# MAIN.net
KiCad netlist of a schematic drawn in Altium Designer
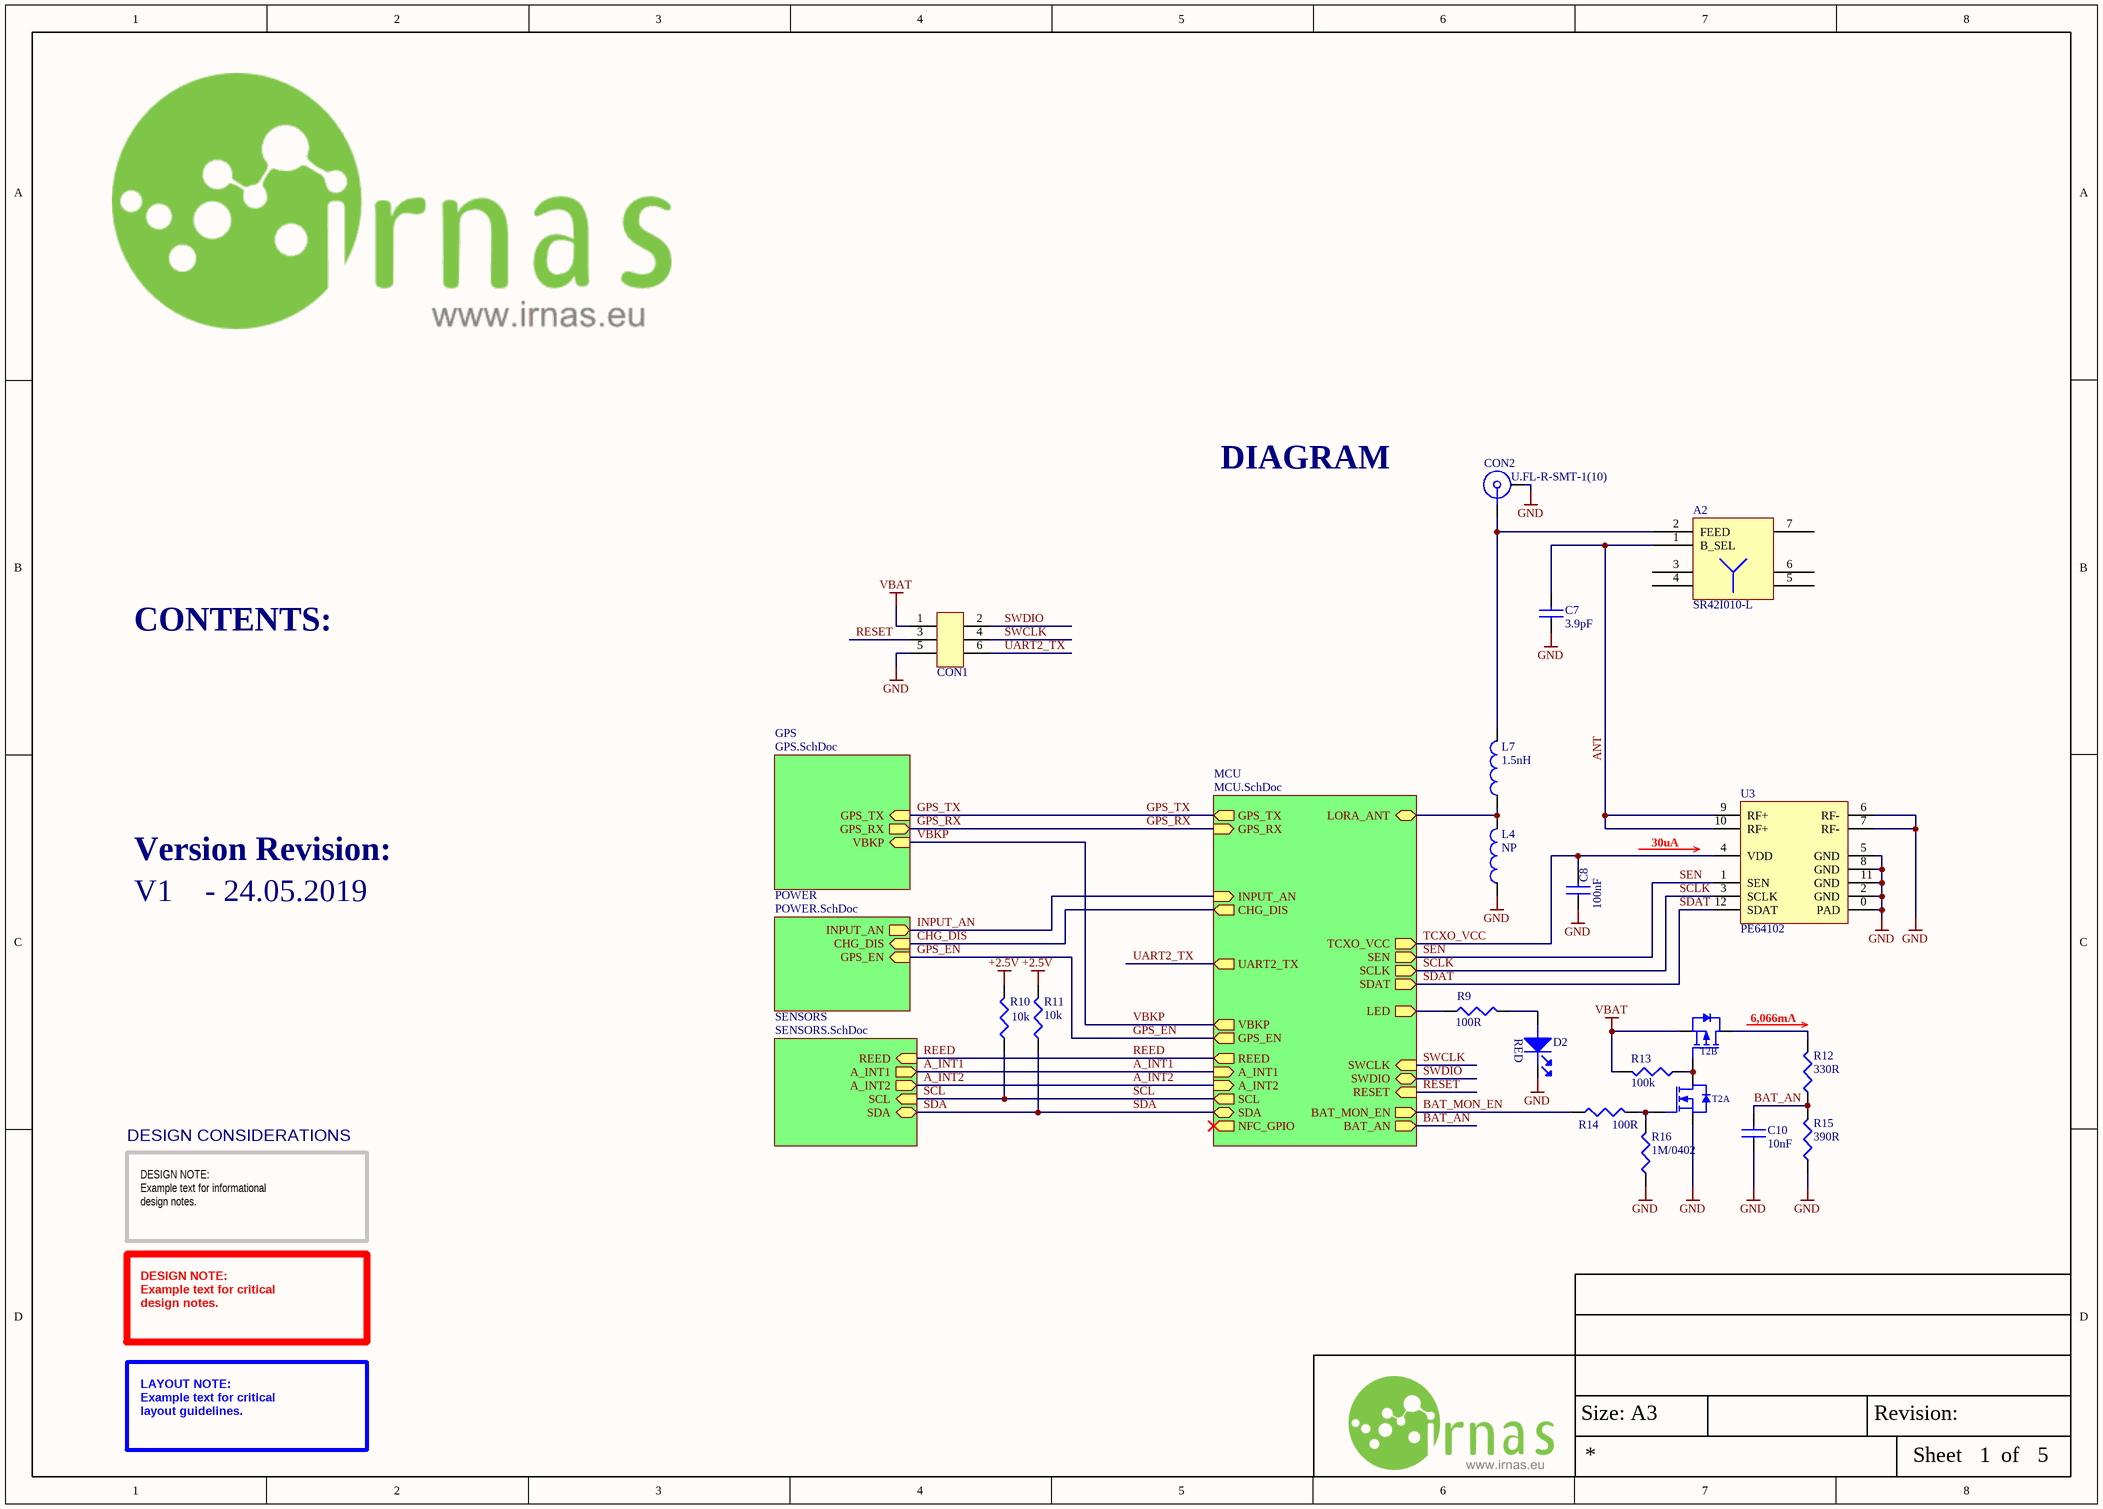
[diagram p0: MAIN.SchDoc]

(export (version "E")
  (design (tool "Eeschema 10.0.6"))
  (components
    (comp (ref "A2")
      (value "SR42I010-L")
      (footprint "SR42I010-L")
      (description "Antenna SMD -4dBi Gain 870MHz/928MHz Automotive 7-Pin SMD T/R")
      (fields (field (name "MANUFACTURER") "Antenova") (field (name "MANUFACTURER PART NUMBER") "SR42I010-R"))
      (libsource (lib "Passive") (part "ANT - SR42I010-L"))
    )
    (comp (ref "C7")
      (value "3.9pF")
      (footprint "CAP0402")
      (description "3.9 pF, 50 V, 0402 [1005 Metric], ± 0.25pF, NP0")
      (fields
        (field (name "MANUFACTURER") "KEMET")
        (field (name "MANUFACTURER PART NUMBER") "MC0402N3R9C500CT")
      )
      (libsource (lib "Passive") (part "C - 3.9pF/0402"))
    )
    (comp (ref "C8")
      (value "100nF")
      (footprint "CAP0402")
      (description "0.1 F, 16 V,  5%, X5R, MC Series")
      (fields
        (field (name "MANUFACTURER") "Multicomp")
        (field (name "MANUFACTURER PART NUMBER") "MC0402X104J160CT")
      )
      (libsource (lib "Passive") (part "C - 100nF/0402"))
    )
    (comp (ref "C10")
      (value "10nF")
      (footprint "CAP0402")
      (description "CAP CER 10000PF 16V X7R 0402")
      (fields
        (field (name "MANUFACTURER") "Murata")
        (field (name "MANUFACTURER PART NUMBER") "GRM155R71C103KA01D")
      )
      (libsource (lib "Passive") (part "C - 10nF/0402"))
    )
    (comp (ref "CON1")
      (value "Tag connect")
      (footprint "TC2030-IDC-NL")
      (libsource (lib "Connectors") (part "tag connecot 6 pin"))
    )
    (comp (ref "CON2")
      (value "U.FL-R-SMT-1(10)")
      (footprint "ufl connector smd")
      (description "RF / Coaxial Connector, U.FL Coaxial, Straight Jack, Surface Mount Vertical, 50 ohm, Brass")
      (fields (field (name "MANUFACTURER") "Hirose"))
      (libsource (lib "Connectors") (part "U.FL-R-SMT-1(10)"))
    )
    (comp (ref "D2")
      (value "LED RED")
      (footprint "LED0603")
      (description "BROADCOM LIMITED - HSMS-C190 - LED, RED, 10MCD, 626NM")
      (fields
        (field (name "MANUFACTURER") "BROADCOM LIMITED")
        (field (name "MANUFACTURER PART NUMBER") "HSMS-C190")
      )
      (libsource (lib "Active") (part "LED - LED RED"))
    )
    (comp (ref "L4")
      (value "NP")
      (footprint "IND0402")
      (description "Inductor RF Chip Multi-Layer 4.3nH 0.3nH 100MHz 8Q-Factor Air 300mA 210mOhm DCR 0402 Paper T/R")
      (fields
        (field (name "MANUFACTURER") "Murata")
        (field (name "MANUFACTURER PART NUMBER") "LQG15HN4N3S02D")
      )
      (libsource (lib "Passive") (part "L - 4.3nH/0402"))
    )
    (comp (ref "L7")
      (value "1.5nH")
      (footprint "IND0402")
      (description "1.5 nH, LQG15HS_02 Series, 1 A, 0402")
      (fields
        (field (name "MANUFACTURER") "Murata")
        (field (name "MANUFACTURER PART NUMBER") "LQG15HS1N5S02D")
      )
      (libsource (lib "Passive") (part "L - 1.5nH/0402"))
    )
    (comp (ref "R9")
      (value "100R")
      (footprint "RES0402")
      (description "100 ohm, 50 V, 0402 [1005 Metric], 62.5 mW,  1%")
      (fields
        (field (name "MANUFACTURER") "Multicomp")
        (field (name "MANUFACTURER PART NUMBER") "MCMR04X1000FTL")
      )
      (libsource (lib "Passive") (part "R - 100R/0402"))
    )
    (comp (ref "R10")
      (value "10k")
      (footprint "RES0402")
      (description "10 kohm, 50 V, 0402 [1005 Metric], 62.5 mW,  1%, MCWR Series")
      (fields
        (field (name "MANUFACTURER") "Multicomp")
        (field (name "MANUFACTURER PART NUMBER") "MCWR04X1002FTL")
      )
      (libsource (lib "Passive") (part "R - 10k/0402"))
    )
    (comp (ref "R11")
      (value "10k")
      (footprint "RES0402")
      (description "10 kohm, 50 V, 0402 [1005 Metric], 62.5 mW,  1%, MCWR Series")
      (fields
        (field (name "MANUFACTURER") "Multicomp")
        (field (name "MANUFACTURER PART NUMBER") "MCWR04X1002FTL")
      )
      (libsource (lib "Passive") (part "R - 10k/0402"))
    )
    (comp (ref "R12")
      (value "330R")
      (footprint "RES0402")
      (fields
        (field (name "MANUFACTURER") "Multicomp")
        (field (name "MANUFACTURER PART NUMBER") "MCMR04X3300FTL")
        (field (name "TOLERANCE") "1%")
      )
      (libsource (lib "Passive") (part "R - 330R/0402"))
    )
    (comp (ref "R13")
      (value "100k")
      (footprint "RES0402")
      (description "100KOHM, 1%, 0.0625W")
      (fields
        (field (name "MANUFACTURER") "Multicomp")
        (field (name "MANUFACTURER PART NUMBER") "MCWR04X1003FTL")
      )
      (libsource (lib "Passive") (part "R - 100k/0402"))
    )
    (comp (ref "R14")
      (value "100R")
      (footprint "RES0402")
      (description "100 ohm, 50 V, 0402 [1005 Metric], 62.5 mW,  1%")
      (fields
        (field (name "MANUFACTURER") "Multicomp")
        (field (name "MANUFACTURER PART NUMBER") "MCMR04X1000FTL")
      )
      (libsource (lib "Passive") (part "R - 100R/0402"))
    )
    (comp (ref "R15")
      (value "390R")
      (footprint "RES0402")
      (description "390 ohm, MCWR Series, 50 V, Thick Film, 62.5 mW")
      (fields (field (name "MANUFACTURER") "Multicomp") (field (name "MANUFACTURER PART NUMBER") "390/0402"))
      (libsource (lib "Passive") (part "R - 390R/0402"))
    )
    (comp (ref "R16")
      (value "1M/0402")
      (footprint "RES0402")
      (description "MCMR04X1004FTL RES, 1M, 1%, 0.0625W, 0402, THICK FILM")
      (fields
        (field (name "MANUFACTURER") "MULTICOMP")
        (field (name "MANUFACTURER PART NUMBER") "MC0063W060311M")
      )
      (libsource (lib "Passive") (part "R - 1M/0402"))
    )
    (comp (ref "T2")
      (value "VT6M1T2CR")
      (footprint "VMT6")
      (description "Dual MOSFET, N and P Channel, 100 mA, 20 V, 2.5 ohm, 4.5 V, 1 V")
      (fields (field (name "AUTHOR") "Ciril Golob"))
      (libsource (lib "Active") (part "T_M - VT6M1T2CR"))
    )
    (comp (ref "U3")
      (value "PE64102")
      (footprint "QFN-12")
      (description "RF IC Digitally Tunable Capacitor General Purpose 100MHz ~ 3GHz SPI Interface 12-QFN (2x2)")
      (fields (field (name "MANUFACTURER") "u-blox") (field (name "MANUFACTURER PART NUMBER") "MAX-M8Q-0"))
      (libsource (lib "Active") (part "RF - PE64102"))
    )
  )
  (nets
    (net (code "1") (name "+2.5V") (class "Default")
      (node (ref "R10") (pin "2") (pinfunction "2_2") (pintype "passive"))
      (node (ref "R11") (pin "2") (pinfunction "2_2") (pintype "passive"))
    )
    (net (code "2") (name "/ANT") (class "Default")
      (node (ref "A2") (pin "1") (pinfunction "B_SEL_1") (pintype "passive"))
      (node (ref "C7") (pin "2") (pinfunction "2_2") (pintype "passive"))
      (node (ref "U3") (pin "10") (pinfunction "RF+_10") (pintype "passive"))
      (node (ref "U3") (pin "9") (pinfunction "RF+_9") (pintype "passive"))
    )
    (net (code "5") (name "/BAT_AN") (class "Default")
      (node (ref "C10") (pin "2") (pinfunction "2_2") (pintype "passive"))
      (node (ref "R12") (pin "1") (pinfunction "1_1") (pintype "passive"))
      (node (ref "R15") (pin "2") (pinfunction "2_2") (pintype "passive"))
    )
    (net (code "6") (name "/BAT_MON_EN") (class "Default")
      (node (ref "R14") (pin "1") (pinfunction "1_1") (pintype "passive"))
    )
    (net (code "12") (name "/LED") (class "Default")
      (node (ref "R9") (pin "1") (pinfunction "1_1") (pintype "passive"))
    )
    (net (code "13") (name "/LORA_ANT") (class "Default")
      (node (ref "L4") (pin "2") (pinfunction "2_2") (pintype "passive"))
      (node (ref "L7") (pin "1") (pinfunction "1_1") (pintype "passive"))
    )
    (net (code "16") (name "/RESET") (class "Default")
      (node (ref "CON1") (pin "3") (pinfunction "3_3") (pintype "open_collector"))
    )
    (net (code "17") (name "/SCL") (class "Default")
      (node (ref "R10") (pin "1") (pinfunction "1_1") (pintype "passive"))
    )
    (net (code "18") (name "/SCLK") (class "Default")
      (node (ref "U3") (pin "3") (pinfunction "SCLK_3") (pintype "passive"))
    )
    (net (code "19") (name "/SDA") (class "Default")
      (node (ref "R11") (pin "1") (pinfunction "1_1") (pintype "passive"))
    )
    (net (code "20") (name "/SDAT") (class "Default")
      (node (ref "U3") (pin "12") (pinfunction "SDAT_12") (pintype "passive"))
    )
    (net (code "21") (name "/SEN") (class "Default")
      (node (ref "U3") (pin "1") (pinfunction "SEN_1") (pintype "passive"))
    )
    (net (code "22") (name "/SWCLK") (class "Default")
      (node (ref "CON1") (pin "4") (pinfunction "4_4") (pintype "open_collector"))
    )
    (net (code "23") (name "/SWDIO") (class "Default")
      (node (ref "CON1") (pin "2") (pinfunction "2_2") (pintype "open_collector"))
    )
    (net (code "24") (name "/TCXO_VCC") (class "Default")
      (node (ref "C8") (pin "2") (pinfunction "2_2") (pintype "passive"))
      (node (ref "U3") (pin "4") (pinfunction "VDD_4") (pintype "passive"))
    )
    (net (code "25") (name "/UART2_TX") (class "Default")
      (node (ref "CON1") (pin "6") (pinfunction "6_6") (pintype "passive"))
    )
    (net (code "27") (name "GND") (class "Default")
      (node (ref "C10") (pin "1") (pinfunction "1_1") (pintype "passive"))
      (node (ref "C7") (pin "1") (pinfunction "1_1") (pintype "passive"))
      (node (ref "C8") (pin "1") (pinfunction "1_1") (pintype "passive"))
      (node (ref "CON1") (pin "5") (pinfunction "5_5") (pintype "open_collector"))
      (node (ref "CON2") (pin "2") (pinfunction "2_2") (pintype "open_collector"))
      (node (ref "D2") (pin "1") (pinfunction "cathode_1") (pintype "passive"))
      (node (ref "L4") (pin "1") (pinfunction "1_1") (pintype "passive"))
      (node (ref "R15") (pin "1") (pinfunction "1_1") (pintype "passive"))
      (node (ref "R16") (pin "1") (pinfunction "1_1") (pintype "passive"))
      (node (ref "T2") (pin "1") (pinfunction "S1_1") (pintype "passive"))
      (node (ref "U3") (pin "0") (pinfunction "PAD_0") (pintype "passive"))
      (node (ref "U3") (pin "11") (pinfunction "GND_11") (pintype "passive"))
      (node (ref "U3") (pin "2") (pinfunction "GND_2") (pintype "passive"))
      (node (ref "U3") (pin "5") (pinfunction "GND_5") (pintype "passive"))
      (node (ref "U3") (pin "6") (pinfunction "RF-_6") (pintype "passive"))
      (node (ref "U3") (pin "7") (pinfunction "RF-_7") (pintype "passive"))
      (node (ref "U3") (pin "8") (pinfunction "GND_8") (pintype "passive"))
    )
    (net (code "28") (name "Net-(A2-FEED)") (class "Default")
      (node (ref "A2") (pin "2") (pinfunction "FEED_2") (pintype "passive"))
      (node (ref "CON2") (pin "1") (pinfunction "1_1") (pintype "open_collector"))
      (node (ref "L7") (pin "2") (pinfunction "2_2") (pintype "passive"))
    )
    (net (code "29") (name "Net-(D2-ANODE)") (class "Default")
      (node (ref "D2") (pin "2") (pinfunction "ANODE_2") (pintype "passive"))
      (node (ref "R9") (pin "2") (pinfunction "2_2") (pintype "passive"))
    )
    (net (code "30") (name "Net-(T2A-D1)") (class "Default")
      (node (ref "R13") (pin "1") (pinfunction "1_1") (pintype "passive"))
      (node (ref "T2") (pin "5") (pinfunction "G2_5") (pintype "passive"))
      (node (ref "T2") (pin "6") (pinfunction "D1_6") (pintype "passive"))
    )
    (net (code "31") (name "Net-(T2A-G1)") (class "Default")
      (node (ref "R14") (pin "2") (pinfunction "2_2") (pintype "passive"))
      (node (ref "R16") (pin "2") (pinfunction "2_2") (pintype "passive"))
      (node (ref "T2") (pin "2") (pinfunction "G1_2") (pintype "passive"))
    )
    (net (code "32") (name "Net-(T2B-D2)") (class "Default")
      (node (ref "R12") (pin "2") (pinfunction "2_2") (pintype "passive"))
      (node (ref "T2") (pin "3") (pinfunction "D2_3") (pintype "passive"))
    )
    (net (code "33") (name "VBAT") (class "Default")
      (node (ref "CON1") (pin "1") (pinfunction "1_1") (pintype "open_collector"))
      (node (ref "R13") (pin "2") (pinfunction "2_2") (pintype "passive"))
      (node (ref "T2") (pin "4") (pinfunction "S2_4") (pintype "passive"))
    )
    (net (code "34") (name "unconnected-(A2-Pad3)") (class "Default")
      (node (ref "A2") (pin "3") (pintype "passive"))
    )
    (net (code "35") (name "unconnected-(A2-Pad4)") (class "Default")
      (node (ref "A2") (pin "4") (pintype "passive"))
    )
    (net (code "36") (name "unconnected-(A2-Pad5)") (class "Default")
      (node (ref "A2") (pin "5") (pintype "passive"))
    )
    (net (code "37") (name "unconnected-(A2-Pad6)") (class "Default")
      (node (ref "A2") (pin "6") (pintype "passive"))
    )
    (net (code "38") (name "unconnected-(A2-Pad7)") (class "Default")
      (node (ref "A2") (pin "7") (pintype "passive"))
    )
  )
)
